# EMFI_HCAL.net
KiCad netlist of a schematic drawn in Altium Designer
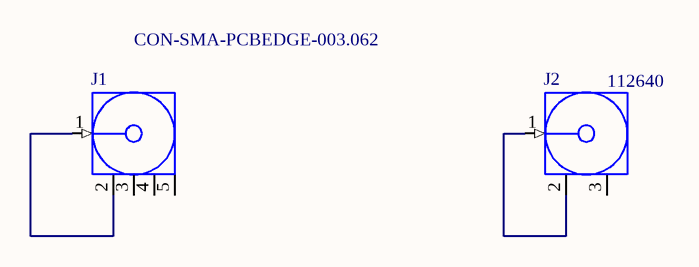
[diagram p0: EMFI_HCAL.SchDoc]

(export (version "E")
  (design (tool "Eeschema 10.0.6"))
  (components
    (comp (ref "J1")
      (value "CON-SMA-PCBEDGE-003.062")
      (footprint "CON-SMA-MALE-PCB-EDGE062")
      (description "SMA MaleEdge Mount Connector for 0.062\" Thick Board")
      (fields (field (name "PART NUMBER") "CON-F-SMA-PCBEDGE-003.062"))
      (libsource (lib "NewAE_AltiumLib") (part "CON-SMA-PCBEDGE-003.062"))
    )
    (comp (ref "J2")
      (value "112640")
      (footprint "BNC_EDGE_JACK")
      (description "BNC Connector Jack, Female Socket 50 Ohm Board Edge, End Launch Solder")
      (fields (field (name "PART NUMBER") "BNC_EDGE_MOUNT"))
      (libsource (lib "NewAE_AltiumLib") (part "CON-BNC-PCBEDGE"))
    )
  )
  (nets
    (net (code "1") (name "Net-(J1-Signal)") (class "Default")
      (node (ref "J1") (pin "1") (pinfunction "Signal_1") (pintype "input"))
      (node (ref "J1") (pin "2") (pinfunction "GND_2") (pintype "power_in"))
    )
    (net (code "2") (name "Net-(J2-Signal)") (class "Default")
      (node (ref "J2") (pin "1") (pinfunction "Signal_1") (pintype "input"))
      (node (ref "J2") (pin "2") (pinfunction "GND_2") (pintype "power_in"))
    )
    (net (code "3") (name "unconnected-(J1-GND-Pad3)") (class "Default")
      (node (ref "J1") (pin "3") (pinfunction "GND_3") (pintype "power_in"))
    )
    (net (code "4") (name "unconnected-(J1-GND-Pad4)") (class "Default")
      (node (ref "J1") (pin "4") (pinfunction "GND_4") (pintype "power_in"))
    )
    (net (code "5") (name "unconnected-(J1-GND-Pad5)") (class "Default")
      (node (ref "J1") (pin "5") (pinfunction "GND_5") (pintype "power_in"))
    )
    (net (code "6") (name "unconnected-(J2-GND-Pad3)") (class "Default")
      (node (ref "J2") (pin "3") (pinfunction "GND_3") (pintype "power_in"))
    )
  )
)
